# Pedalboard_Interface_Shield_v0_2.net
KiCad netlist of a schematic drawn in EAGLE
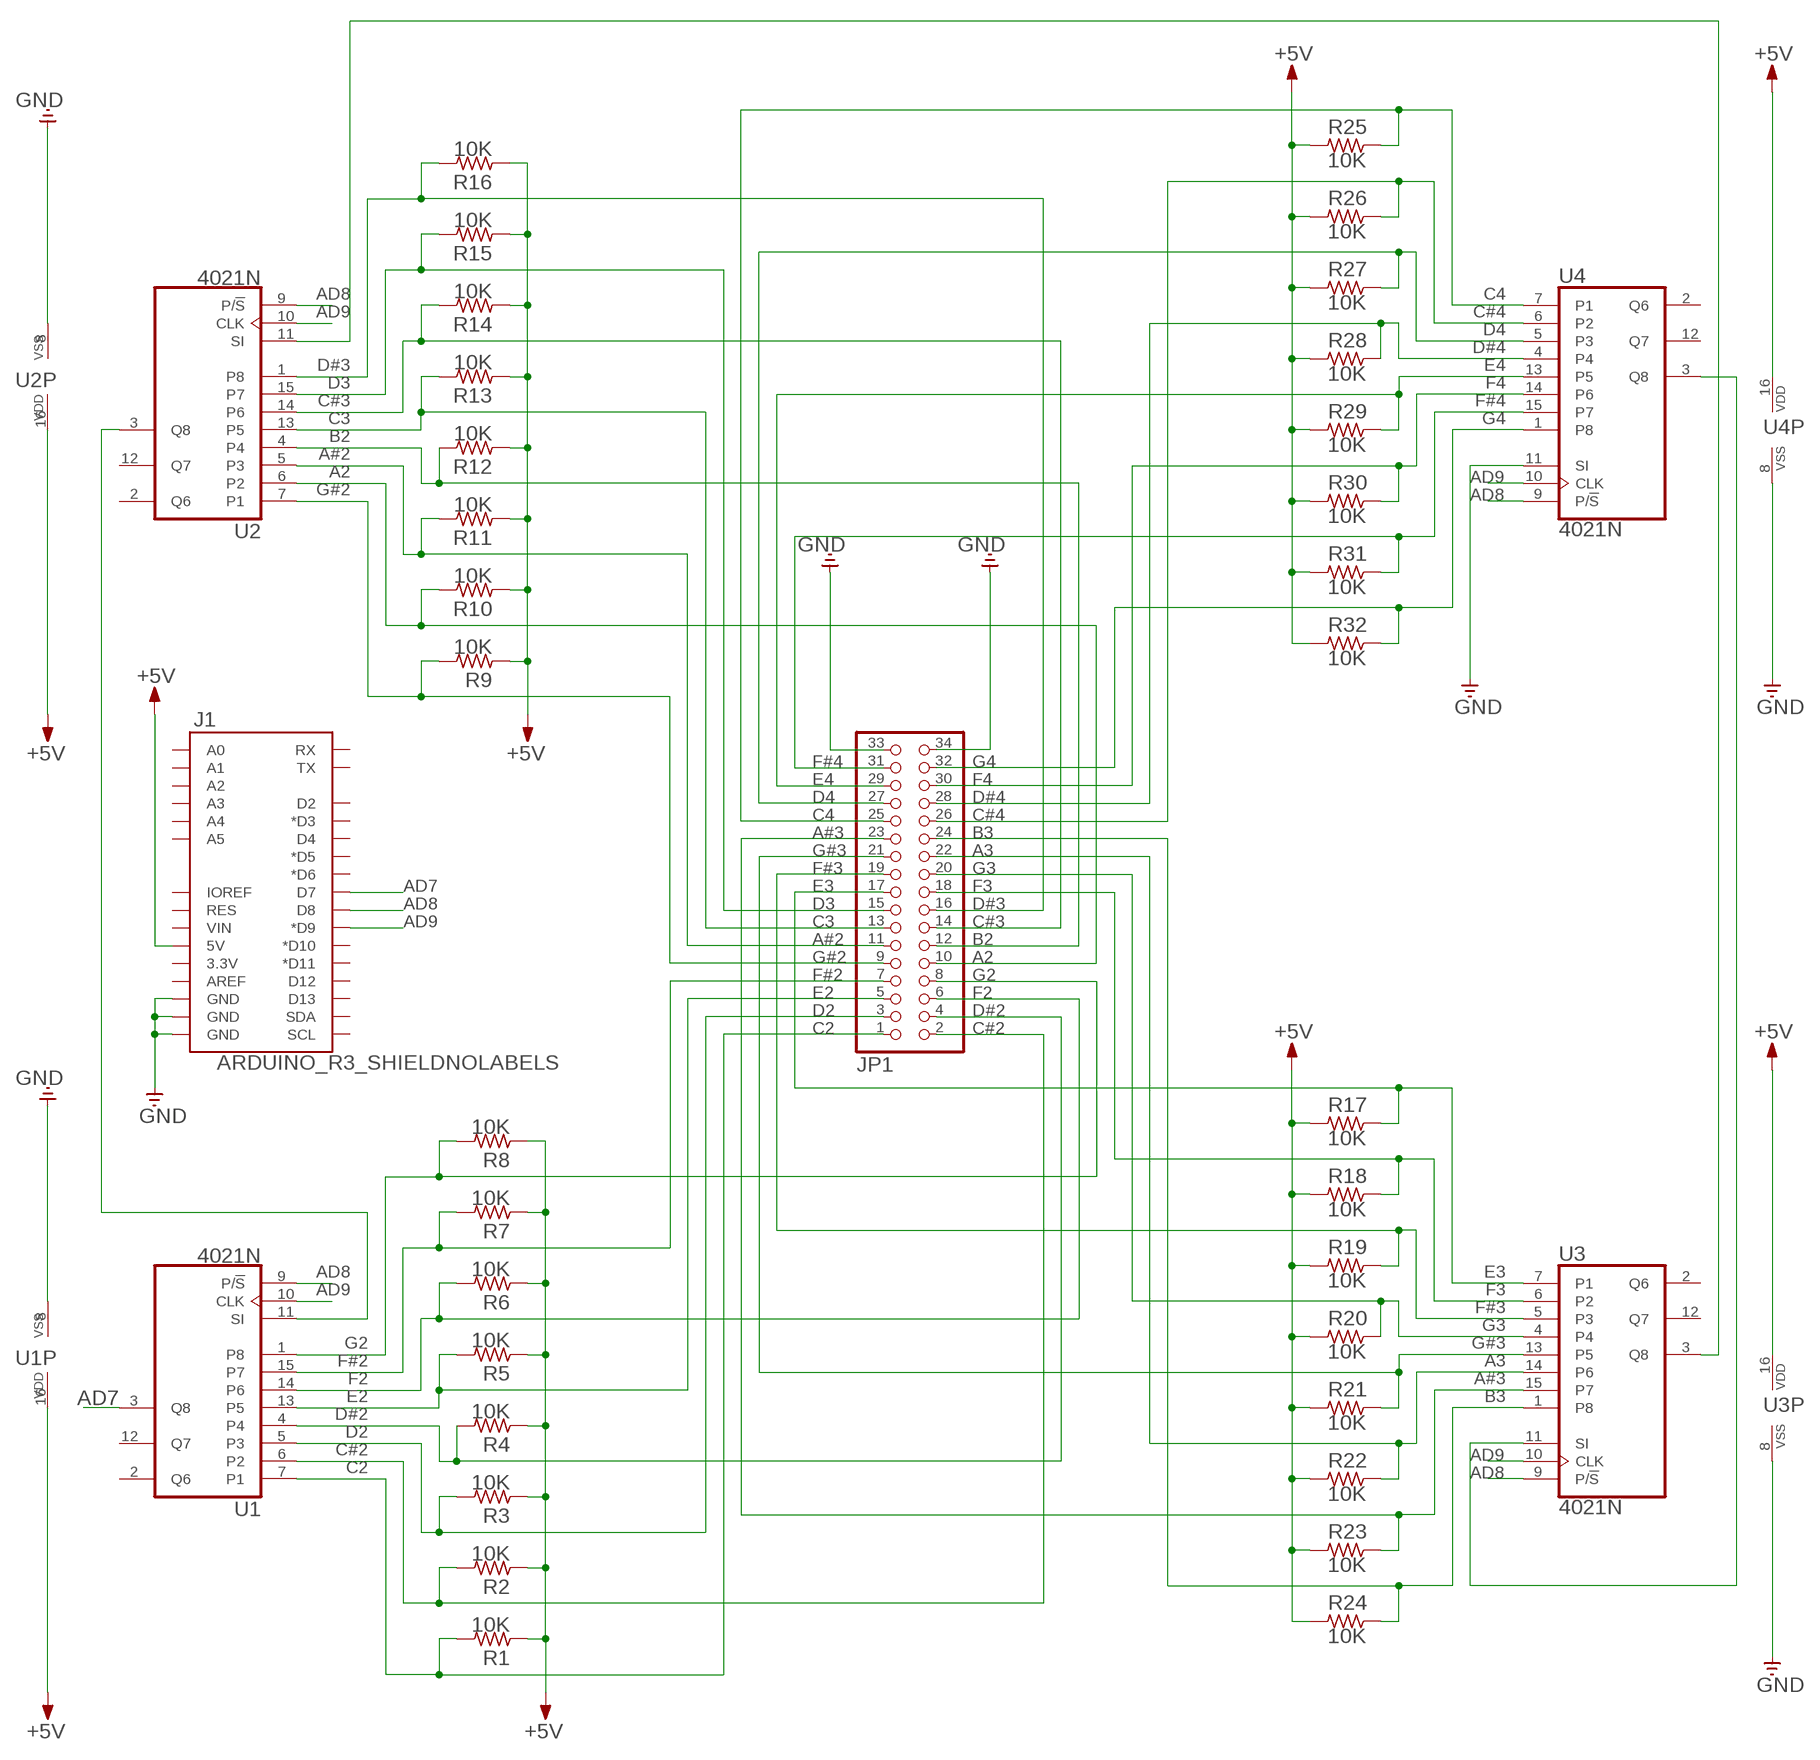
[diagram p0: schematic, sheet 1]

(export (version "E")
  (design (tool "Eeschema 10.0.6"))
  (components
    (comp (ref "J1")
      (value "ARDUINO_R3_SHIELDNOLABELS")
      (footprint "eagle-import:UNO_R3_SHIELD_NOLABELS")
      (libsource (lib "eagle-import") (part "ARDUINO_R3_SHIELDNOLABELS"))
    )
    (comp (ref "JP1")
      (value "PINHD-2X17")
      (footprint "eagle-import:2X17")
      (libsource (lib "eagle-import") (part "PINHD-2X17"))
    )
    (comp (ref "R1")
      (value "10K")
      (footprint "eagle-import:0207_2V")
      (libsource (lib "eagle-import") (part "R_X0207/2V"))
    )
    (comp (ref "R2")
      (value "10K")
      (footprint "eagle-import:0207_2V")
      (libsource (lib "eagle-import") (part "R_X0207/2V"))
    )
    (comp (ref "R3")
      (value "10K")
      (footprint "eagle-import:0207_2V")
      (libsource (lib "eagle-import") (part "R_X0207/2V"))
    )
    (comp (ref "R4")
      (value "10K")
      (footprint "eagle-import:0207_2V")
      (libsource (lib "eagle-import") (part "R_X0207/2V"))
    )
    (comp (ref "R5")
      (value "10K")
      (footprint "eagle-import:0207_2V")
      (libsource (lib "eagle-import") (part "R_X0207/2V"))
    )
    (comp (ref "R6")
      (value "10K")
      (footprint "eagle-import:0207_2V")
      (libsource (lib "eagle-import") (part "R_X0207/2V"))
    )
    (comp (ref "R7")
      (value "10K")
      (footprint "eagle-import:0207_2V")
      (libsource (lib "eagle-import") (part "R_X0207/2V"))
    )
    (comp (ref "R8")
      (value "10K")
      (footprint "eagle-import:0207_2V")
      (libsource (lib "eagle-import") (part "R_X0207/2V"))
    )
    (comp (ref "R9")
      (value "10K")
      (footprint "eagle-import:0207_2V")
      (libsource (lib "eagle-import") (part "R_X0207/2V"))
    )
    (comp (ref "R10")
      (value "10K")
      (footprint "eagle-import:0207_2V")
      (libsource (lib "eagle-import") (part "R_X0207/2V"))
    )
    (comp (ref "R11")
      (value "10K")
      (footprint "eagle-import:0207_2V")
      (libsource (lib "eagle-import") (part "R_X0207/2V"))
    )
    (comp (ref "R12")
      (value "10K")
      (footprint "eagle-import:0207_2V")
      (libsource (lib "eagle-import") (part "R_X0207/2V"))
    )
    (comp (ref "R13")
      (value "10K")
      (footprint "eagle-import:0207_2V")
      (libsource (lib "eagle-import") (part "R_X0207/2V"))
    )
    (comp (ref "R14")
      (value "10K")
      (footprint "eagle-import:0207_2V")
      (libsource (lib "eagle-import") (part "R_X0207/2V"))
    )
    (comp (ref "R15")
      (value "10K")
      (footprint "eagle-import:0207_2V")
      (libsource (lib "eagle-import") (part "R_X0207/2V"))
    )
    (comp (ref "R16")
      (value "10K")
      (footprint "eagle-import:0207_2V")
      (libsource (lib "eagle-import") (part "R_X0207/2V"))
    )
    (comp (ref "R17")
      (value "10K")
      (footprint "eagle-import:0207_2V")
      (libsource (lib "eagle-import") (part "R_X0207/2V"))
    )
    (comp (ref "R18")
      (value "10K")
      (footprint "eagle-import:0207_2V")
      (libsource (lib "eagle-import") (part "R_X0207/2V"))
    )
    (comp (ref "R19")
      (value "10K")
      (footprint "eagle-import:0207_2V")
      (libsource (lib "eagle-import") (part "R_X0207/2V"))
    )
    (comp (ref "R20")
      (value "10K")
      (footprint "eagle-import:0207_2V")
      (libsource (lib "eagle-import") (part "R_X0207/2V"))
    )
    (comp (ref "R21")
      (value "10K")
      (footprint "eagle-import:0207_2V")
      (libsource (lib "eagle-import") (part "R_X0207/2V"))
    )
    (comp (ref "R22")
      (value "10K")
      (footprint "eagle-import:0207_2V")
      (libsource (lib "eagle-import") (part "R_X0207/2V"))
    )
    (comp (ref "R23")
      (value "10K")
      (footprint "eagle-import:0207_2V")
      (libsource (lib "eagle-import") (part "R_X0207/2V"))
    )
    (comp (ref "R24")
      (value "10K")
      (footprint "eagle-import:0207_2V")
      (libsource (lib "eagle-import") (part "R_X0207/2V"))
    )
    (comp (ref "R25")
      (value "10K")
      (footprint "eagle-import:0207_2V")
      (libsource (lib "eagle-import") (part "R_X0207/2V"))
    )
    (comp (ref "R26")
      (value "10K")
      (footprint "eagle-import:0207_2V")
      (libsource (lib "eagle-import") (part "R_X0207/2V"))
    )
    (comp (ref "R27")
      (value "10K")
      (footprint "eagle-import:0207_2V")
      (libsource (lib "eagle-import") (part "R_X0207/2V"))
    )
    (comp (ref "R28")
      (value "10K")
      (footprint "eagle-import:0207_2V")
      (libsource (lib "eagle-import") (part "R_X0207/2V"))
    )
    (comp (ref "R29")
      (value "10K")
      (footprint "eagle-import:0207_2V")
      (libsource (lib "eagle-import") (part "R_X0207/2V"))
    )
    (comp (ref "R30")
      (value "10K")
      (footprint "eagle-import:0207_2V")
      (libsource (lib "eagle-import") (part "R_X0207/2V"))
    )
    (comp (ref "R31")
      (value "10K")
      (footprint "eagle-import:0207_2V")
      (libsource (lib "eagle-import") (part "R_X0207/2V"))
    )
    (comp (ref "R32")
      (value "10K")
      (footprint "eagle-import:0207_2V")
      (libsource (lib "eagle-import") (part "R_X0207/2V"))
    )
    (comp (ref "U1")
      (value "4021N")
      (footprint "eagle-import:DIL16")
      (libsource (lib "eagle-import") (part "4021N"))
    )
    (comp (ref "U2")
      (value "4021N")
      (footprint "eagle-import:DIL16")
      (libsource (lib "eagle-import") (part "4021N"))
    )
    (comp (ref "U3")
      (value "4021N")
      (footprint "eagle-import:DIL16")
      (libsource (lib "eagle-import") (part "4021N"))
    )
    (comp (ref "U4")
      (value "4021N")
      (footprint "eagle-import:DIL16")
      (libsource (lib "eagle-import") (part "4021N"))
    )
  )
  (nets
    (net (code "1") (name "+5V") (class "Default")
      (node (ref "J1") (pin "5V") (pinfunction "5V_5V") (pintype "bidirectional"))
      (node (ref "R1") (pin "1") (pinfunction "1_1") (pintype "passive"))
      (node (ref "R10") (pin "1") (pinfunction "1_1") (pintype "passive"))
      (node (ref "R11") (pin "1") (pinfunction "1_1") (pintype "passive"))
      (node (ref "R12") (pin "1") (pinfunction "1_1") (pintype "passive"))
      (node (ref "R13") (pin "1") (pinfunction "1_1") (pintype "passive"))
      (node (ref "R14") (pin "1") (pinfunction "1_1") (pintype "passive"))
      (node (ref "R15") (pin "1") (pinfunction "1_1") (pintype "passive"))
      (node (ref "R16") (pin "1") (pinfunction "1_1") (pintype "passive"))
      (node (ref "R17") (pin "1") (pinfunction "1_1") (pintype "passive"))
      (node (ref "R18") (pin "1") (pinfunction "1_1") (pintype "passive"))
      (node (ref "R19") (pin "1") (pinfunction "1_1") (pintype "passive"))
      (node (ref "R2") (pin "1") (pinfunction "1_1") (pintype "passive"))
      (node (ref "R20") (pin "1") (pinfunction "1_1") (pintype "passive"))
      (node (ref "R21") (pin "1") (pinfunction "1_1") (pintype "passive"))
      (node (ref "R22") (pin "1") (pinfunction "1_1") (pintype "passive"))
      (node (ref "R23") (pin "1") (pinfunction "1_1") (pintype "passive"))
      (node (ref "R24") (pin "1") (pinfunction "1_1") (pintype "passive"))
      (node (ref "R25") (pin "1") (pinfunction "1_1") (pintype "passive"))
      (node (ref "R26") (pin "1") (pinfunction "1_1") (pintype "passive"))
      (node (ref "R27") (pin "1") (pinfunction "1_1") (pintype "passive"))
      (node (ref "R28") (pin "1") (pinfunction "1_1") (pintype "passive"))
      (node (ref "R29") (pin "1") (pinfunction "1_1") (pintype "passive"))
      (node (ref "R3") (pin "1") (pinfunction "1_1") (pintype "passive"))
      (node (ref "R30") (pin "1") (pinfunction "1_1") (pintype "passive"))
      (node (ref "R31") (pin "1") (pinfunction "1_1") (pintype "passive"))
      (node (ref "R32") (pin "1") (pinfunction "1_1") (pintype "passive"))
      (node (ref "R4") (pin "1") (pinfunction "1_1") (pintype "passive"))
      (node (ref "R5") (pin "1") (pinfunction "1_1") (pintype "passive"))
      (node (ref "R6") (pin "1") (pinfunction "1_1") (pintype "passive"))
      (node (ref "R7") (pin "1") (pinfunction "1_1") (pintype "passive"))
      (node (ref "R8") (pin "1") (pinfunction "1_1") (pintype "passive"))
      (node (ref "R9") (pin "1") (pinfunction "1_1") (pintype "passive"))
      (node (ref "U1") (pin "16") (pinfunction "VDD_16") (pintype "power_in"))
      (node (ref "U2") (pin "16") (pinfunction "VDD_16") (pintype "power_in"))
      (node (ref "U3") (pin "16") (pinfunction "VDD_16") (pintype "power_in"))
      (node (ref "U4") (pin "16") (pinfunction "VDD_16") (pintype "power_in"))
    )
    (net (code "2") (name "/A#2") (class "Default")
      (node (ref "JP1") (pin "11") (pinfunction "11_11") (pintype "passive"))
      (node (ref "R11") (pin "2") (pinfunction "2_2") (pintype "passive"))
      (node (ref "U2") (pin "5") (pinfunction "P3_5") (pintype "input"))
    )
    (net (code "3") (name "/A#3") (class "Default")
      (node (ref "JP1") (pin "23") (pinfunction "23_23") (pintype "passive"))
      (node (ref "R23") (pin "2") (pinfunction "2_2") (pintype "passive"))
      (node (ref "U3") (pin "15") (pinfunction "P7_15") (pintype "input"))
    )
    (net (code "4") (name "/A2") (class "Default")
      (node (ref "JP1") (pin "10") (pinfunction "10_10") (pintype "passive"))
      (node (ref "R10") (pin "2") (pinfunction "2_2") (pintype "passive"))
      (node (ref "U2") (pin "6") (pinfunction "P2_6") (pintype "input"))
    )
    (net (code "5") (name "/A3") (class "Default")
      (node (ref "JP1") (pin "22") (pinfunction "22_22") (pintype "passive"))
      (node (ref "R22") (pin "2") (pinfunction "2_2") (pintype "passive"))
      (node (ref "U3") (pin "14") (pinfunction "P6_14") (pintype "input"))
    )
    (net (code "6") (name "/AD7") (class "Default")
      (node (ref "J1") (pin "D7") (pinfunction "D7_D7") (pintype "bidirectional"))
      (node (ref "U1") (pin "3") (pinfunction "Q8_3") (pintype "output"))
    )
    (net (code "7") (name "/AD8") (class "Default")
      (node (ref "J1") (pin "D8") (pinfunction "D8_D8") (pintype "bidirectional"))
      (node (ref "U1") (pin "9") (pinfunction "P/~{S}_9") (pintype "input"))
      (node (ref "U2") (pin "9") (pinfunction "P/~{S}_9") (pintype "input"))
      (node (ref "U3") (pin "9") (pinfunction "P/~{S}_9") (pintype "input"))
      (node (ref "U4") (pin "9") (pinfunction "P/~{S}_9") (pintype "input"))
    )
    (net (code "8") (name "/AD9") (class "Default")
      (node (ref "J1") (pin "D9") (pinfunction "*D9_D9") (pintype "bidirectional"))
      (node (ref "U1") (pin "10") (pinfunction "CLK_10") (pintype "input"))
      (node (ref "U2") (pin "10") (pinfunction "CLK_10") (pintype "input"))
      (node (ref "U3") (pin "10") (pinfunction "CLK_10") (pintype "input"))
      (node (ref "U4") (pin "10") (pinfunction "CLK_10") (pintype "input"))
    )
    (net (code "9") (name "/B2") (class "Default")
      (node (ref "JP1") (pin "12") (pinfunction "12_12") (pintype "passive"))
      (node (ref "R12") (pin "2") (pinfunction "2_2") (pintype "passive"))
      (node (ref "U2") (pin "4") (pinfunction "P4_4") (pintype "input"))
    )
    (net (code "10") (name "/B3") (class "Default")
      (node (ref "JP1") (pin "24") (pinfunction "24_24") (pintype "passive"))
      (node (ref "R24") (pin "2") (pinfunction "2_2") (pintype "passive"))
      (node (ref "U3") (pin "1") (pinfunction "P8_1") (pintype "input"))
    )
    (net (code "11") (name "/C#2") (class "Default")
      (node (ref "JP1") (pin "2") (pinfunction "2_2") (pintype "passive"))
      (node (ref "R2") (pin "2") (pinfunction "2_2") (pintype "passive"))
      (node (ref "U1") (pin "6") (pinfunction "P2_6") (pintype "input"))
    )
    (net (code "12") (name "/C#3") (class "Default")
      (node (ref "JP1") (pin "14") (pinfunction "14_14") (pintype "passive"))
      (node (ref "R14") (pin "2") (pinfunction "2_2") (pintype "passive"))
      (node (ref "U2") (pin "14") (pinfunction "P6_14") (pintype "input"))
    )
    (net (code "13") (name "/C#4") (class "Default")
      (node (ref "JP1") (pin "26") (pinfunction "26_26") (pintype "passive"))
      (node (ref "R26") (pin "2") (pinfunction "2_2") (pintype "passive"))
      (node (ref "U4") (pin "6") (pinfunction "P2_6") (pintype "input"))
    )
    (net (code "14") (name "/C2") (class "Default")
      (node (ref "JP1") (pin "1") (pinfunction "1_1") (pintype "passive"))
      (node (ref "R1") (pin "2") (pinfunction "2_2") (pintype "passive"))
      (node (ref "U1") (pin "7") (pinfunction "P1_7") (pintype "input"))
    )
    (net (code "15") (name "/C3") (class "Default")
      (node (ref "JP1") (pin "13") (pinfunction "13_13") (pintype "passive"))
      (node (ref "R13") (pin "2") (pinfunction "2_2") (pintype "passive"))
      (node (ref "U2") (pin "13") (pinfunction "P5_13") (pintype "input"))
    )
    (net (code "16") (name "/C4") (class "Default")
      (node (ref "JP1") (pin "25") (pinfunction "25_25") (pintype "passive"))
      (node (ref "R25") (pin "2") (pinfunction "2_2") (pintype "passive"))
      (node (ref "U4") (pin "7") (pinfunction "P1_7") (pintype "input"))
    )
    (net (code "17") (name "/D#2") (class "Default")
      (node (ref "JP1") (pin "4") (pinfunction "4_4") (pintype "passive"))
      (node (ref "R4") (pin "2") (pinfunction "2_2") (pintype "passive"))
      (node (ref "U1") (pin "4") (pinfunction "P4_4") (pintype "input"))
    )
    (net (code "18") (name "/D#3") (class "Default")
      (node (ref "JP1") (pin "16") (pinfunction "16_16") (pintype "passive"))
      (node (ref "R16") (pin "2") (pinfunction "2_2") (pintype "passive"))
      (node (ref "U2") (pin "1") (pinfunction "P8_1") (pintype "input"))
    )
    (net (code "19") (name "/D#4") (class "Default")
      (node (ref "JP1") (pin "28") (pinfunction "28_28") (pintype "passive"))
      (node (ref "R28") (pin "2") (pinfunction "2_2") (pintype "passive"))
      (node (ref "U4") (pin "4") (pinfunction "P4_4") (pintype "input"))
    )
    (net (code "20") (name "/D2") (class "Default")
      (node (ref "JP1") (pin "3") (pinfunction "3_3") (pintype "passive"))
      (node (ref "R3") (pin "2") (pinfunction "2_2") (pintype "passive"))
      (node (ref "U1") (pin "5") (pinfunction "P3_5") (pintype "input"))
    )
    (net (code "21") (name "/D3") (class "Default")
      (node (ref "JP1") (pin "15") (pinfunction "15_15") (pintype "passive"))
      (node (ref "R15") (pin "2") (pinfunction "2_2") (pintype "passive"))
      (node (ref "U2") (pin "15") (pinfunction "P7_15") (pintype "input"))
    )
    (net (code "22") (name "/D4") (class "Default")
      (node (ref "JP1") (pin "27") (pinfunction "27_27") (pintype "passive"))
      (node (ref "R27") (pin "2") (pinfunction "2_2") (pintype "passive"))
      (node (ref "U4") (pin "5") (pinfunction "P3_5") (pintype "input"))
    )
    (net (code "23") (name "/E2") (class "Default")
      (node (ref "JP1") (pin "5") (pinfunction "5_5") (pintype "passive"))
      (node (ref "R5") (pin "2") (pinfunction "2_2") (pintype "passive"))
      (node (ref "U1") (pin "13") (pinfunction "P5_13") (pintype "input"))
    )
    (net (code "24") (name "/E3") (class "Default")
      (node (ref "JP1") (pin "17") (pinfunction "17_17") (pintype "passive"))
      (node (ref "R17") (pin "2") (pinfunction "2_2") (pintype "passive"))
      (node (ref "U3") (pin "7") (pinfunction "P1_7") (pintype "input"))
    )
    (net (code "25") (name "/E4") (class "Default")
      (node (ref "JP1") (pin "29") (pinfunction "29_29") (pintype "passive"))
      (node (ref "R29") (pin "2") (pinfunction "2_2") (pintype "passive"))
      (node (ref "U4") (pin "13") (pinfunction "P5_13") (pintype "input"))
    )
    (net (code "26") (name "/F#2") (class "Default")
      (node (ref "JP1") (pin "7") (pinfunction "7_7") (pintype "passive"))
      (node (ref "R7") (pin "2") (pinfunction "2_2") (pintype "passive"))
      (node (ref "U1") (pin "15") (pinfunction "P7_15") (pintype "input"))
    )
    (net (code "27") (name "/F#3") (class "Default")
      (node (ref "JP1") (pin "19") (pinfunction "19_19") (pintype "passive"))
      (node (ref "R19") (pin "2") (pinfunction "2_2") (pintype "passive"))
      (node (ref "U3") (pin "5") (pinfunction "P3_5") (pintype "input"))
    )
    (net (code "28") (name "/F#4") (class "Default")
      (node (ref "JP1") (pin "31") (pinfunction "31_31") (pintype "passive"))
      (node (ref "R31") (pin "2") (pinfunction "2_2") (pintype "passive"))
      (node (ref "U4") (pin "15") (pinfunction "P7_15") (pintype "input"))
    )
    (net (code "29") (name "/F2") (class "Default")
      (node (ref "JP1") (pin "6") (pinfunction "6_6") (pintype "passive"))
      (node (ref "R6") (pin "2") (pinfunction "2_2") (pintype "passive"))
      (node (ref "U1") (pin "14") (pinfunction "P6_14") (pintype "input"))
    )
    (net (code "30") (name "/F3") (class "Default")
      (node (ref "JP1") (pin "18") (pinfunction "18_18") (pintype "passive"))
      (node (ref "R18") (pin "2") (pinfunction "2_2") (pintype "passive"))
      (node (ref "U3") (pin "6") (pinfunction "P2_6") (pintype "input"))
    )
    (net (code "31") (name "/F4") (class "Default")
      (node (ref "JP1") (pin "30") (pinfunction "30_30") (pintype "passive"))
      (node (ref "R30") (pin "2") (pinfunction "2_2") (pintype "passive"))
      (node (ref "U4") (pin "14") (pinfunction "P6_14") (pintype "input"))
    )
    (net (code "32") (name "/G#2") (class "Default")
      (node (ref "JP1") (pin "9") (pinfunction "9_9") (pintype "passive"))
      (node (ref "R9") (pin "2") (pinfunction "2_2") (pintype "passive"))
      (node (ref "U2") (pin "7") (pinfunction "P1_7") (pintype "input"))
    )
    (net (code "33") (name "/G#3") (class "Default")
      (node (ref "JP1") (pin "21") (pinfunction "21_21") (pintype "passive"))
      (node (ref "R21") (pin "2") (pinfunction "2_2") (pintype "passive"))
      (node (ref "U3") (pin "13") (pinfunction "P5_13") (pintype "input"))
    )
    (net (code "34") (name "/G2") (class "Default")
      (node (ref "JP1") (pin "8") (pinfunction "8_8") (pintype "passive"))
      (node (ref "R8") (pin "2") (pinfunction "2_2") (pintype "passive"))
      (node (ref "U1") (pin "1") (pinfunction "P8_1") (pintype "input"))
    )
    (net (code "35") (name "/G3") (class "Default")
      (node (ref "JP1") (pin "20") (pinfunction "20_20") (pintype "passive"))
      (node (ref "R20") (pin "2") (pinfunction "2_2") (pintype "passive"))
      (node (ref "U3") (pin "4") (pinfunction "P4_4") (pintype "input"))
    )
    (net (code "36") (name "/G4") (class "Default")
      (node (ref "JP1") (pin "32") (pinfunction "32_32") (pintype "passive"))
      (node (ref "R32") (pin "2") (pinfunction "2_2") (pintype "passive"))
      (node (ref "U4") (pin "1") (pinfunction "P8_1") (pintype "input"))
    )
    (net (code "37") (name "GND") (class "Default")
      (node (ref "J1") (pin "GND@0") (pinfunction "GND_GND@0") (pintype "bidirectional"))
      (node (ref "J1") (pin "GND@1") (pinfunction "GND_GND@1") (pintype "bidirectional"))
      (node (ref "J1") (pin "GND@2") (pinfunction "GND_GND@2") (pintype "bidirectional"))
      (node (ref "JP1") (pin "33") (pinfunction "33_33") (pintype "passive"))
      (node (ref "JP1") (pin "34") (pinfunction "34_34") (pintype "passive"))
      (node (ref "U1") (pin "8") (pinfunction "VSS_8") (pintype "power_in"))
      (node (ref "U2") (pin "8") (pinfunction "VSS_8") (pintype "power_in"))
      (node (ref "U3") (pin "8") (pinfunction "VSS_8") (pintype "power_in"))
      (node (ref "U4") (pin "11") (pinfunction "SI_11") (pintype "input"))
      (node (ref "U4") (pin "8") (pinfunction "VSS_8") (pintype "power_in"))
    )
    (net (code "38") (name "Net-(U1A-SI)") (class "Default")
      (node (ref "U1") (pin "11") (pinfunction "SI_11") (pintype "input"))
      (node (ref "U2") (pin "3") (pinfunction "Q8_3") (pintype "output"))
    )
    (net (code "39") (name "Net-(U2A-SI)") (class "Default")
      (node (ref "U2") (pin "11") (pinfunction "SI_11") (pintype "input"))
      (node (ref "U3") (pin "3") (pinfunction "Q8_3") (pintype "output"))
    )
    (net (code "40") (name "Net-(U3A-SI)") (class "Default")
      (node (ref "U3") (pin "11") (pinfunction "SI_11") (pintype "input"))
      (node (ref "U4") (pin "3") (pinfunction "Q8_3") (pintype "output"))
    )
    (net (code "41") (name "unconnected-(J1-*D3-PadD3)") (class "Default")
      (node (ref "J1") (pin "D3") (pinfunction "*D3_D3") (pintype "bidirectional"))
    )
    (net (code "42") (name "unconnected-(J1-*D5-PadD5)") (class "Default")
      (node (ref "J1") (pin "D5") (pinfunction "*D5_D5") (pintype "bidirectional"))
    )
    (net (code "43") (name "unconnected-(J1-*D6-PadD6)") (class "Default")
      (node (ref "J1") (pin "D6") (pinfunction "*D6_D6") (pintype "bidirectional"))
    )
    (net (code "44") (name "unconnected-(J1-*D10-PadD10)") (class "Default")
      (node (ref "J1") (pin "D10") (pinfunction "*D10_D10") (pintype "bidirectional"))
    )
    (net (code "45") (name "unconnected-(J1-*D11-PadD11)") (class "Default")
      (node (ref "J1") (pin "D11") (pinfunction "*D11_D11") (pintype "bidirectional"))
    )
    (net (code "46") (name "unconnected-(J1-Pad3.3V)") (class "Default")
      (node (ref "J1") (pin "3.3V") (pinfunction "3.3V_3.3V") (pintype "bidirectional"))
    )
    (net (code "47") (name "unconnected-(J1-PadA0)") (class "Default")
      (node (ref "J1") (pin "A0") (pinfunction "A0_A0") (pintype "bidirectional"))
    )
    (net (code "48") (name "unconnected-(J1-PadA1)") (class "Default")
      (node (ref "J1") (pin "A1") (pinfunction "A1_A1") (pintype "bidirectional"))
    )
    (net (code "49") (name "unconnected-(J1-PadA2)") (class "Default")
      (node (ref "J1") (pin "A2") (pinfunction "A2_A2") (pintype "bidirectional"))
    )
    (net (code "50") (name "unconnected-(J1-PadA3)") (class "Default")
      (node (ref "J1") (pin "A3") (pinfunction "A3_A3") (pintype "bidirectional"))
    )
    (net (code "51") (name "unconnected-(J1-PadA4)") (class "Default")
      (node (ref "J1") (pin "A4") (pinfunction "A4_A4") (pintype "bidirectional"))
    )
    (net (code "52") (name "unconnected-(J1-PadA5)") (class "Default")
      (node (ref "J1") (pin "A5") (pinfunction "A5_A5") (pintype "bidirectional"))
    )
    (net (code "53") (name "unconnected-(J1-PadAREF)") (class "Default")
      (node (ref "J1") (pin "AREF") (pinfunction "AREF_AREF") (pintype "bidirectional"))
    )
    (net (code "54") (name "unconnected-(J1-PadD2)") (class "Default")
      (node (ref "J1") (pin "D2") (pinfunction "D2_D2") (pintype "bidirectional"))
    )
    (net (code "55") (name "unconnected-(J1-PadD4)") (class "Default")
      (node (ref "J1") (pin "D4") (pinfunction "D4_D4") (pintype "bidirectional"))
    )
    (net (code "56") (name "unconnected-(J1-PadD12)") (class "Default")
      (node (ref "J1") (pin "D12") (pinfunction "D12_D12") (pintype "bidirectional"))
    )
    (net (code "57") (name "unconnected-(J1-PadD13)") (class "Default")
      (node (ref "J1") (pin "D13") (pinfunction "D13_D13") (pintype "bidirectional"))
    )
    (net (code "58") (name "unconnected-(J1-PadIOREF)") (class "Default")
      (node (ref "J1") (pin "IOREF") (pinfunction "IOREF_IOREF") (pintype "bidirectional"))
    )
    (net (code "59") (name "unconnected-(J1-PadRES)") (class "Default")
      (node (ref "J1") (pin "RES") (pinfunction "RES_RES") (pintype "bidirectional"))
    )
    (net (code "60") (name "unconnected-(J1-PadRX)") (class "Default")
      (node (ref "J1") (pin "RX") (pinfunction "RX_RX") (pintype "bidirectional"))
    )
    (net (code "61") (name "unconnected-(J1-PadSCL)") (class "Default")
      (node (ref "J1") (pin "SCL") (pinfunction "SCL_SCL") (pintype "bidirectional"))
    )
    (net (code "62") (name "unconnected-(J1-PadSDA)") (class "Default")
      (node (ref "J1") (pin "SDA") (pinfunction "SDA_SDA") (pintype "bidirectional"))
    )
    (net (code "63") (name "unconnected-(J1-PadTX)") (class "Default")
      (node (ref "J1") (pin "TX") (pinfunction "TX_TX") (pintype "bidirectional"))
    )
    (net (code "64") (name "unconnected-(J1-PadVIN)") (class "Default")
      (node (ref "J1") (pin "VIN") (pinfunction "VIN_VIN") (pintype "bidirectional"))
    )
    (net (code "65") (name "unconnected-(U1A-Q6-Pad2)") (class "Default")
      (node (ref "U1") (pin "2") (pinfunction "Q6_2") (pintype "output"))
    )
    (net (code "66") (name "unconnected-(U1A-Q7-Pad12)") (class "Default")
      (node (ref "U1") (pin "12") (pinfunction "Q7_12") (pintype "output"))
    )
    (net (code "67") (name "unconnected-(U2A-Q6-Pad2)") (class "Default")
      (node (ref "U2") (pin "2") (pinfunction "Q6_2") (pintype "output"))
    )
    (net (code "68") (name "unconnected-(U2A-Q7-Pad12)") (class "Default")
      (node (ref "U2") (pin "12") (pinfunction "Q7_12") (pintype "output"))
    )
    (net (code "69") (name "unconnected-(U3A-Q6-Pad2)") (class "Default")
      (node (ref "U3") (pin "2") (pinfunction "Q6_2") (pintype "output"))
    )
    (net (code "70") (name "unconnected-(U3A-Q7-Pad12)") (class "Default")
      (node (ref "U3") (pin "12") (pinfunction "Q7_12") (pintype "output"))
    )
    (net (code "71") (name "unconnected-(U4A-Q6-Pad2)") (class "Default")
      (node (ref "U4") (pin "2") (pinfunction "Q6_2") (pintype "output"))
    )
    (net (code "72") (name "unconnected-(U4A-Q7-Pad12)") (class "Default")
      (node (ref "U4") (pin "12") (pinfunction "Q7_12") (pintype "output"))
    )
  )
)
